# Adafruit_VS1053_Breakout.net
KiCad netlist of a schematic drawn in EAGLE
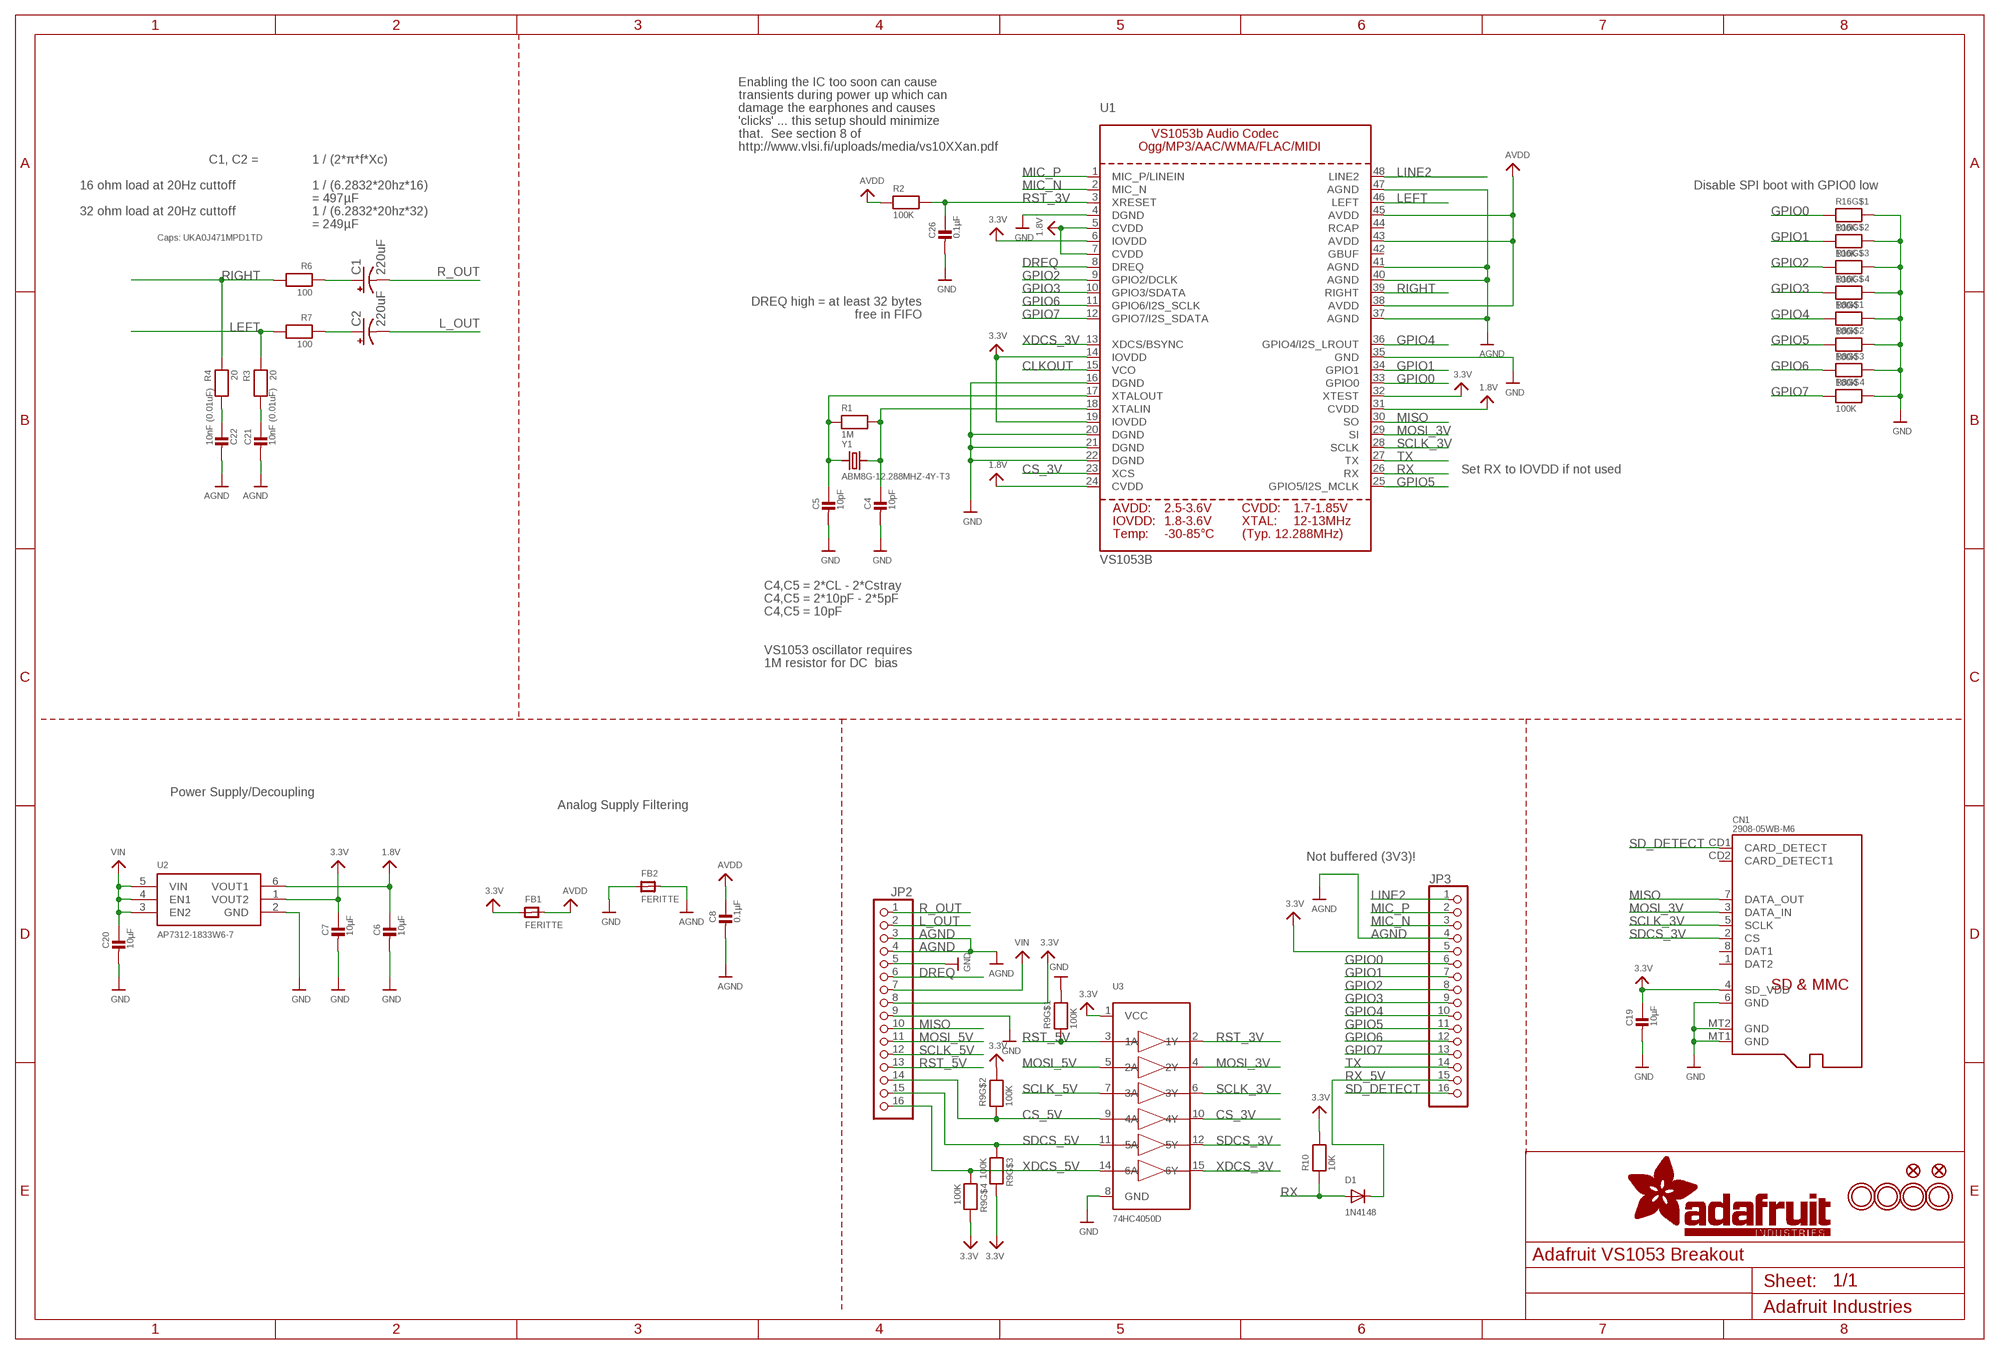
[diagram p0: schematic, sheet 1]

(export (version "E")
  (design (tool "Eeschema 10.0.6"))
  (components
    (comp (ref "C1")
      (value "220uF")
      (footprint "eagle-import:PANASONIC_C")
      (libsource (lib "eagle-import") (part "CPOL-USC"))
    )
    (comp (ref "C2")
      (value "220uF")
      (footprint "eagle-import:PANASONIC_C")
      (libsource (lib "eagle-import") (part "CPOL-USC"))
    )
    (comp (ref "C4")
      (value "10pF")
      (footprint "eagle-import:_0805MP")
      (libsource (lib "eagle-import") (part "CAP_CERAMIC_0805MP"))
    )
    (comp (ref "C5")
      (value "10pF")
      (footprint "eagle-import:_0805MP")
      (libsource (lib "eagle-import") (part "CAP_CERAMIC_0805MP"))
    )
    (comp (ref "C6")
      (value "10µF")
      (footprint "eagle-import:_0805MP")
      (libsource (lib "eagle-import") (part "CAP_CERAMIC_0805MP"))
    )
    (comp (ref "C7")
      (value "10µF")
      (footprint "eagle-import:_0805MP")
      (libsource (lib "eagle-import") (part "CAP_CERAMIC_0805MP"))
    )
    (comp (ref "C8")
      (value "0.1µF")
      (footprint "eagle-import:_0805MP")
      (libsource (lib "eagle-import") (part "CAP_CERAMIC_0805MP"))
    )
    (comp (ref "C19")
      (value "10µF")
      (footprint "eagle-import:_0805MP")
      (libsource (lib "eagle-import") (part "CAP_CERAMIC_0805MP"))
    )
    (comp (ref "C20")
      (value "10µF")
      (footprint "eagle-import:_0805MP")
      (libsource (lib "eagle-import") (part "CAP_CERAMIC_0805MP"))
    )
    (comp (ref "C21")
      (value "10nF (0.01uF)")
      (footprint "eagle-import:_0805MP")
      (libsource (lib "eagle-import") (part "CAP_CERAMIC_0805MP"))
    )
    (comp (ref "C22")
      (value "10nF (0.01uF)")
      (footprint "eagle-import:_0805MP")
      (libsource (lib "eagle-import") (part "CAP_CERAMIC_0805MP"))
    )
    (comp (ref "C26")
      (value "0.1µF")
      (footprint "eagle-import:_0805MP")
      (libsource (lib "eagle-import") (part "CAP_CERAMIC_0805MP"))
    )
    (comp (ref "CN1")
      (value "2908-05WB-M6")
      (footprint "eagle-import:MICROSD")
      (libsource (lib "eagle-import") (part "MICROSD"))
    )
    (comp (ref "D1")
      (value "1N4148")
      (footprint "eagle-import:SOD-323")
      (libsource (lib "eagle-import") (part "DIODESOD-323"))
    )
    (comp (ref "FB1")
      (value "FERITTE")
      (footprint "eagle-import:_0805MP")
      (libsource (lib "eagle-import") (part "FERRITE_0805MP"))
    )
    (comp (ref "FB2")
      (value "FERITTE")
      (footprint "eagle-import:_0805MP")
      (libsource (lib "eagle-import") (part "FERRITE_0805MP"))
    )
    (comp (ref "FID1")
      (value "FIDUCIAL\"\"")
      (footprint "eagle-import:FIDUCIAL_1MM")
      (libsource (lib "eagle-import") (part "FIDUCIAL{dblquote}{dblquote}"))
    )
    (comp (ref "FID2")
      (value "FIDUCIAL\"\"")
      (footprint "eagle-import:FIDUCIAL_1MM")
      (libsource (lib "eagle-import") (part "FIDUCIAL{dblquote}{dblquote}"))
    )
    (comp (ref "JP2")
      (value "HEADER-1X16ROUND")
      (footprint "eagle-import:1X16_ROUND")
      (libsource (lib "eagle-import") (part "HEADER-1X16ROUND"))
    )
    (comp (ref "JP3")
      (value "HEADER-1X16ROUND")
      (footprint "eagle-import:1X16_ROUND")
      (libsource (lib "eagle-import") (part "HEADER-1X16ROUND"))
    )
    (comp (ref "R1")
      (value "1M")
      (footprint "eagle-import:_0805MP")
      (libsource (lib "eagle-import") (part "RESISTOR_0805MP"))
    )
    (comp (ref "R2")
      (value "100K")
      (footprint "eagle-import:_0805MP")
      (libsource (lib "eagle-import") (part "RESISTOR_0805MP"))
    )
    (comp (ref "R3")
      (value "20")
      (footprint "eagle-import:_0805MP")
      (libsource (lib "eagle-import") (part "RESISTOR_0805MP"))
    )
    (comp (ref "R4")
      (value "20")
      (footprint "eagle-import:_0805MP")
      (libsource (lib "eagle-import") (part "RESISTOR_0805MP"))
    )
    (comp (ref "R6")
      (value "100")
      (footprint "eagle-import:_0805MP")
      (libsource (lib "eagle-import") (part "RESISTOR_0805MP"))
    )
    (comp (ref "R7")
      (value "100")
      (footprint "eagle-import:_0805MP")
      (libsource (lib "eagle-import") (part "RESISTOR_0805MP"))
    )
    (comp (ref "R8")
      (value "100K")
      (footprint "eagle-import:RESPACK_4X0603")
      (libsource (lib "eagle-import") (part "RESISTOR_4PACK"))
    )
    (comp (ref "R9")
      (value "100K")
      (footprint "eagle-import:RESPACK_4X0603")
      (libsource (lib "eagle-import") (part "RESISTOR_4PACK"))
    )
    (comp (ref "R10")
      (value "10K")
      (footprint "eagle-import:0805-NO")
      (libsource (lib "eagle-import") (part "RESISTOR0805_NOOUTLINE"))
    )
    (comp (ref "R16")
      (value "100K")
      (footprint "eagle-import:RESPACK_4X0603")
      (libsource (lib "eagle-import") (part "RESISTOR_4PACK"))
    )
    (comp (ref "U$50")
      (value "MOUNTINGHOLE3.0THIN")
      (footprint "eagle-import:MOUNTINGHOLE_3.0_PLATEDTHIN")
      (libsource (lib "eagle-import") (part "MOUNTINGHOLE3.0THIN"))
    )
    (comp (ref "U$51")
      (value "MOUNTINGHOLE3.0THIN")
      (footprint "eagle-import:MOUNTINGHOLE_3.0_PLATEDTHIN")
      (libsource (lib "eagle-import") (part "MOUNTINGHOLE3.0THIN"))
    )
    (comp (ref "U$52")
      (value "MOUNTINGHOLE3.0THIN")
      (footprint "eagle-import:MOUNTINGHOLE_3.0_PLATEDTHIN")
      (libsource (lib "eagle-import") (part "MOUNTINGHOLE3.0THIN"))
    )
    (comp (ref "U$53")
      (value "MOUNTINGHOLE3.0THIN")
      (footprint "eagle-import:MOUNTINGHOLE_3.0_PLATEDTHIN")
      (libsource (lib "eagle-import") (part "MOUNTINGHOLE3.0THIN"))
    )
    (comp (ref "U1")
      (value "VS1053B")
      (footprint "eagle-import:LQFP48")
      (libsource (lib "eagle-import") (part "VS1053B"))
    )
    (comp (ref "U2")
      (value "AP7312-1833W6-7")
      (footprint "eagle-import:SOT23-6")
      (libsource (lib "eagle-import") (part "VREG_SOT23-6_DUALAP7312"))
    )
    (comp (ref "U3")
      (value "74HC4050D")
      (footprint "eagle-import:SOIC16")
      (libsource (lib "eagle-import") (part "74HC4050D"))
    )
    (comp (ref "Y1")
      (value "ABM8G-12.288MHZ-4Y-T3")
      (footprint "eagle-import:CRYSTAL_3.2X2.5")
      (libsource (lib "eagle-import") (part "CRYSTAL3.2X2.5"))
    )
  )
  (nets
    (net (code "1") (name "/CLKOUT") (class "Default")
      (node (ref "U1") (pin "15") (pinfunction "VCO_15") (pintype "bidirectional"))
    )
    (net (code "2") (name "/CS_3V") (class "Default")
      (node (ref "U1") (pin "23") (pinfunction "XCS_23") (pintype "bidirectional"))
      (node (ref "U3") (pin "10") (pinfunction "4Y_10") (pintype "bidirectional"))
    )
    (net (code "3") (name "/CS_5V") (class "Default")
      (node (ref "JP2") (pin "14") (pinfunction "14_14") (pintype "passive"))
      (node (ref "R9") (pin "2") (pinfunction "1_2") (pintype "passive"))
      (node (ref "U3") (pin "9") (pinfunction "4A_9") (pintype "bidirectional"))
    )
    (net (code "4") (name "/DREQ") (class "Default")
      (node (ref "JP2") (pin "6") (pinfunction "6_6") (pintype "passive"))
      (node (ref "U1") (pin "8") (pinfunction "DREQ_8") (pintype "bidirectional"))
    )
    (net (code "5") (name "/GPIO0") (class "Default")
      (node (ref "JP3") (pin "6") (pinfunction "6_6") (pintype "passive"))
      (node (ref "R16") (pin "1") (pinfunction "1_1") (pintype "passive"))
      (node (ref "U1") (pin "33") (pinfunction "GPIO0_33") (pintype "bidirectional"))
    )
    (net (code "6") (name "/GPIO1") (class "Default")
      (node (ref "JP3") (pin "7") (pinfunction "7_7") (pintype "passive"))
      (node (ref "R16") (pin "2") (pinfunction "1_2") (pintype "passive"))
      (node (ref "U1") (pin "34") (pinfunction "GPIO1_34") (pintype "bidirectional"))
    )
    (net (code "7") (name "/GPIO2") (class "Default")
      (node (ref "JP3") (pin "8") (pinfunction "8_8") (pintype "passive"))
      (node (ref "R16") (pin "3") (pinfunction "1_3") (pintype "passive"))
      (node (ref "U1") (pin "9") (pinfunction "GPIO2/DCLK_9") (pintype "bidirectional"))
    )
    (net (code "8") (name "/GPIO3") (class "Default")
      (node (ref "JP3") (pin "9") (pinfunction "9_9") (pintype "passive"))
      (node (ref "R16") (pin "4") (pinfunction "1_4") (pintype "passive"))
      (node (ref "U1") (pin "10") (pinfunction "GPIO3/SDATA_10") (pintype "bidirectional"))
    )
    (net (code "9") (name "/GPIO4") (class "Default")
      (node (ref "JP3") (pin "10") (pinfunction "10_10") (pintype "passive"))
      (node (ref "R8") (pin "1") (pinfunction "1_1") (pintype "passive"))
      (node (ref "U1") (pin "36") (pinfunction "GPIO4/I2S_LROUT_36") (pintype "bidirectional"))
    )
    (net (code "10") (name "/GPIO5") (class "Default")
      (node (ref "JP3") (pin "11") (pinfunction "11_11") (pintype "passive"))
      (node (ref "R8") (pin "2") (pinfunction "1_2") (pintype "passive"))
      (node (ref "U1") (pin "25") (pinfunction "GPIO5/I2S_MCLK_25") (pintype "bidirectional"))
    )
    (net (code "11") (name "/GPIO6") (class "Default")
      (node (ref "JP3") (pin "12") (pinfunction "12_12") (pintype "passive"))
      (node (ref "R8") (pin "3") (pinfunction "1_3") (pintype "passive"))
      (node (ref "U1") (pin "11") (pinfunction "GPIO6/I2S_SCLK_11") (pintype "bidirectional"))
    )
    (net (code "12") (name "/GPIO7") (class "Default")
      (node (ref "JP3") (pin "13") (pinfunction "13_13") (pintype "passive"))
      (node (ref "R8") (pin "4") (pinfunction "1_4") (pintype "passive"))
      (node (ref "U1") (pin "12") (pinfunction "GPIO7/I2S_SDATA_12") (pintype "bidirectional"))
    )
    (net (code "13") (name "/LEFT") (class "Default")
      (node (ref "R3") (pin "1") (pinfunction "1_1") (pintype "passive"))
      (node (ref "R7") (pin "2") (pinfunction "2_2") (pintype "passive"))
      (node (ref "U1") (pin "46") (pinfunction "LEFT_46") (pintype "bidirectional"))
    )
    (net (code "14") (name "/LINE2") (class "Default")
      (node (ref "JP3") (pin "1") (pinfunction "1_1") (pintype "passive"))
      (node (ref "U1") (pin "48") (pinfunction "LINE2_48") (pintype "bidirectional"))
    )
    (net (code "15") (name "/L_OUT") (class "Default")
      (node (ref "C2") (pin "-") (pinfunction "-_-") (pintype "passive"))
      (node (ref "JP2") (pin "2") (pinfunction "2_2") (pintype "passive"))
    )
    (net (code "16") (name "/MIC_N") (class "Default")
      (node (ref "JP3") (pin "3") (pinfunction "3_3") (pintype "passive"))
      (node (ref "U1") (pin "2") (pinfunction "MIC_N_2") (pintype "bidirectional"))
    )
    (net (code "17") (name "/MIC_P") (class "Default")
      (node (ref "JP3") (pin "2") (pinfunction "2_2") (pintype "passive"))
      (node (ref "U1") (pin "1") (pinfunction "MIC_P/LINEIN_1") (pintype "bidirectional"))
    )
    (net (code "18") (name "/MISO") (class "Default")
      (node (ref "CN1") (pin "7") (pinfunction "DATA_OUT_7") (pintype "output"))
      (node (ref "JP2") (pin "10") (pinfunction "10_10") (pintype "passive"))
      (node (ref "U1") (pin "30") (pinfunction "SO_30") (pintype "bidirectional"))
    )
    (net (code "19") (name "/MOSI_3V") (class "Default")
      (node (ref "CN1") (pin "3") (pinfunction "DATA_IN_3") (pintype "input"))
      (node (ref "U1") (pin "29") (pinfunction "SI_29") (pintype "bidirectional"))
      (node (ref "U3") (pin "4") (pinfunction "2Y_4") (pintype "bidirectional"))
    )
    (net (code "20") (name "/MOSI_5V") (class "Default")
      (node (ref "JP2") (pin "11") (pinfunction "11_11") (pintype "passive"))
      (node (ref "U3") (pin "5") (pinfunction "2A_5") (pintype "bidirectional"))
    )
    (net (code "21") (name "/RIGHT") (class "Default")
      (node (ref "R4") (pin "1") (pinfunction "1_1") (pintype "passive"))
      (node (ref "R6") (pin "2") (pinfunction "2_2") (pintype "passive"))
      (node (ref "U1") (pin "39") (pinfunction "RIGHT_39") (pintype "bidirectional"))
    )
    (net (code "22") (name "/RST_3V") (class "Default")
      (node (ref "C26") (pin "1") (pinfunction "1_1") (pintype "passive"))
      (node (ref "R2") (pin "2") (pinfunction "2_2") (pintype "passive"))
      (node (ref "U1") (pin "3") (pinfunction "XRESET_3") (pintype "bidirectional"))
      (node (ref "U3") (pin "2") (pinfunction "1Y_2") (pintype "bidirectional"))
    )
    (net (code "23") (name "/RST_5V") (class "Default")
      (node (ref "JP2") (pin "13") (pinfunction "13_13") (pintype "passive"))
      (node (ref "R9") (pin "1") (pinfunction "1_1") (pintype "passive"))
      (node (ref "U3") (pin "3") (pinfunction "1A_3") (pintype "bidirectional"))
    )
    (net (code "24") (name "/RX") (class "Default")
      (node (ref "D1") (pin "A") (pinfunction "A_A") (pintype "passive"))
      (node (ref "R10") (pin "1") (pinfunction "1_1") (pintype "passive"))
      (node (ref "U1") (pin "26") (pinfunction "RX_26") (pintype "bidirectional"))
    )
    (net (code "25") (name "/RX_5V") (class "Default")
      (node (ref "D1") (pin "C") (pinfunction "C_C") (pintype "passive"))
      (node (ref "JP3") (pin "15") (pinfunction "15_15") (pintype "passive"))
    )
    (net (code "26") (name "/R_OUT") (class "Default")
      (node (ref "C1") (pin "-") (pinfunction "-_-") (pintype "passive"))
      (node (ref "JP2") (pin "1") (pinfunction "1_1") (pintype "passive"))
    )
    (net (code "27") (name "/SCLK_3V") (class "Default")
      (node (ref "CN1") (pin "5") (pinfunction "SCLK_5") (pintype "input"))
      (node (ref "U1") (pin "28") (pinfunction "SCLK_28") (pintype "bidirectional"))
      (node (ref "U3") (pin "6") (pinfunction "3Y_6") (pintype "bidirectional"))
    )
    (net (code "28") (name "/SCLK_5V") (class "Default")
      (node (ref "JP2") (pin "12") (pinfunction "12_12") (pintype "passive"))
      (node (ref "U3") (pin "7") (pinfunction "3A_7") (pintype "bidirectional"))
    )
    (net (code "29") (name "/SDCS_3V") (class "Default")
      (node (ref "CN1") (pin "2") (pinfunction "CS_2") (pintype "input"))
      (node (ref "U3") (pin "12") (pinfunction "5Y_12") (pintype "bidirectional"))
    )
    (net (code "30") (name "/SDCS_5V") (class "Default")
      (node (ref "JP2") (pin "15") (pinfunction "15_15") (pintype "passive"))
      (node (ref "R9") (pin "3") (pinfunction "1_3") (pintype "passive"))
      (node (ref "U3") (pin "11") (pinfunction "5A_11") (pintype "bidirectional"))
    )
    (net (code "31") (name "/SD_DETECT") (class "Default")
      (node (ref "CN1") (pin "CD1") (pinfunction "CARD_DETECT_CD1") (pintype "passive"))
      (node (ref "JP3") (pin "16") (pinfunction "16_16") (pintype "passive"))
    )
    (net (code "32") (name "/TX") (class "Default")
      (node (ref "JP3") (pin "14") (pinfunction "14_14") (pintype "passive"))
      (node (ref "U1") (pin "27") (pinfunction "TX_27") (pintype "bidirectional"))
    )
    (net (code "33") (name "/XDCS_3V") (class "Default")
      (node (ref "U1") (pin "13") (pinfunction "XDCS/BSYNC_13") (pintype "bidirectional"))
      (node (ref "U3") (pin "15") (pinfunction "6Y_15") (pintype "bidirectional"))
    )
    (net (code "34") (name "/XDCS_5V") (class "Default")
      (node (ref "JP2") (pin "16") (pinfunction "16_16") (pintype "passive"))
      (node (ref "R9") (pin "4") (pinfunction "1_4") (pintype "passive"))
      (node (ref "U3") (pin "14") (pinfunction "6A_14") (pintype "bidirectional"))
    )
    (net (code "35") (name "1.8V") (class "Default")
      (node (ref "C6") (pin "1") (pinfunction "1_1") (pintype "passive"))
      (node (ref "U1") (pin "24") (pinfunction "CVDD_24") (pintype "power_in"))
      (node (ref "U1") (pin "31") (pinfunction "CVDD_31") (pintype "power_in"))
      (node (ref "U1") (pin "5") (pinfunction "CVDD_5") (pintype "power_in"))
      (node (ref "U1") (pin "7") (pinfunction "CVDD_7") (pintype "power_in"))
      (node (ref "U2") (pin "6") (pinfunction "VOUT1_6") (pintype "bidirectional"))
    )
    (net (code "36") (name "3.3V") (class "Default")
      (node (ref "C19") (pin "1") (pinfunction "1_1") (pintype "passive"))
      (node (ref "C7") (pin "1") (pinfunction "1_1") (pintype "passive"))
      (node (ref "CN1") (pin "4") (pinfunction "SD_VDD_4") (pintype "power_in"))
      (node (ref "FB1") (pin "1") (pinfunction "P$1_1") (pintype "passive"))
      (node (ref "JP2") (pin "8") (pinfunction "8_8") (pintype "passive"))
      (node (ref "JP3") (pin "5") (pinfunction "5_5") (pintype "passive"))
      (node (ref "R10") (pin "2") (pinfunction "2_2") (pintype "passive"))
      (node (ref "R9") (pin "5") (pinfunction "2_5") (pintype "passive"))
      (node (ref "R9") (pin "6") (pinfunction "2_6") (pintype "passive"))
      (node (ref "R9") (pin "7") (pinfunction "2_7") (pintype "passive"))
      (node (ref "U1") (pin "14") (pinfunction "IOVDD_14") (pintype "power_in"))
      (node (ref "U1") (pin "19") (pinfunction "IOVDD_19") (pintype "power_in"))
      (node (ref "U1") (pin "32") (pinfunction "XTEST_32") (pintype "bidirectional"))
      (node (ref "U1") (pin "6") (pinfunction "IOVDD_6") (pintype "power_in"))
      (node (ref "U2") (pin "1") (pinfunction "VOUT2_1") (pintype "bidirectional"))
      (node (ref "U3") (pin "1") (pinfunction "VCC_1") (pintype "bidirectional"))
    )
    (net (code "37") (name "AGND") (class "Default")
      (node (ref "C21") (pin "2") (pinfunction "2_2") (pintype "passive"))
      (node (ref "C22") (pin "2") (pinfunction "2_2") (pintype "passive"))
      (node (ref "C8") (pin "2") (pinfunction "2_2") (pintype "passive"))
      (node (ref "FB2") (pin "2") (pinfunction "P$2_2") (pintype "passive"))
      (node (ref "JP2") (pin "3") (pinfunction "3_3") (pintype "passive"))
      (node (ref "JP2") (pin "4") (pinfunction "4_4") (pintype "passive"))
      (node (ref "JP3") (pin "4") (pinfunction "4_4") (pintype "passive"))
      (node (ref "U1") (pin "37") (pinfunction "AGND_37") (pintype "power_in"))
      (node (ref "U1") (pin "40") (pinfunction "AGND_40") (pintype "power_in"))
      (node (ref "U1") (pin "41") (pinfunction "AGND_41") (pintype "power_in"))
      (node (ref "U1") (pin "47") (pinfunction "AGND_47") (pintype "power_in"))
    )
    (net (code "38") (name "AVDD") (class "Default")
      (node (ref "C8") (pin "1") (pinfunction "1_1") (pintype "passive"))
      (node (ref "FB1") (pin "2") (pinfunction "P$2_2") (pintype "passive"))
      (node (ref "R2") (pin "1") (pinfunction "1_1") (pintype "passive"))
      (node (ref "U1") (pin "38") (pinfunction "AVDD_38") (pintype "power_in"))
      (node (ref "U1") (pin "43") (pinfunction "AVDD_43") (pintype "power_in"))
      (node (ref "U1") (pin "45") (pinfunction "AVDD_45") (pintype "power_in"))
    )
    (net (code "39") (name "GND") (class "Default")
      (node (ref "C19") (pin "2") (pinfunction "2_2") (pintype "passive"))
      (node (ref "C20") (pin "2") (pinfunction "2_2") (pintype "passive"))
      (node (ref "C26") (pin "2") (pinfunction "2_2") (pintype "passive"))
      (node (ref "C4") (pin "2") (pinfunction "2_2") (pintype "passive"))
      (node (ref "C5") (pin "2") (pinfunction "2_2") (pintype "passive"))
      (node (ref "C6") (pin "2") (pinfunction "2_2") (pintype "passive"))
      (node (ref "C7") (pin "2") (pinfunction "2_2") (pintype "passive"))
      (node (ref "CN1") (pin "6") (pinfunction "GND_6") (pintype "power_in"))
      (node (ref "CN1") (pin "MT1") (pinfunction "GND_MT1") (pintype "power_in"))
      (node (ref "CN1") (pin "MT2") (pinfunction "GND_MT2") (pintype "power_in"))
      (node (ref "FB2") (pin "1") (pinfunction "P$1_1") (pintype "passive"))
      (node (ref "JP2") (pin "5") (pinfunction "5_5") (pintype "passive"))
      (node (ref "JP2") (pin "9") (pinfunction "9_9") (pintype "passive"))
      (node (ref "R16") (pin "5") (pinfunction "2_5") (pintype "passive"))
      (node (ref "R16") (pin "6") (pinfunction "2_6") (pintype "passive"))
      (node (ref "R16") (pin "7") (pinfunction "2_7") (pintype "passive"))
      (node (ref "R16") (pin "8") (pinfunction "2_8") (pintype "passive"))
      (node (ref "R8") (pin "5") (pinfunction "2_5") (pintype "passive"))
      (node (ref "R8") (pin "6") (pinfunction "2_6") (pintype "passive"))
      (node (ref "R8") (pin "7") (pinfunction "2_7") (pintype "passive"))
      (node (ref "R8") (pin "8") (pinfunction "2_8") (pintype "passive"))
      (node (ref "R9") (pin "8") (pinfunction "2_8") (pintype "passive"))
      (node (ref "U1") (pin "16") (pinfunction "DGND_16") (pintype "power_in"))
      (node (ref "U1") (pin "20") (pinfunction "DGND_20") (pintype "power_in"))
      (node (ref "U1") (pin "21") (pinfunction "DGND_21") (pintype "power_in"))
      (node (ref "U1") (pin "22") (pinfunction "DGND_22") (pintype "power_in"))
      (node (ref "U1") (pin "35") (pinfunction "GND_35") (pintype "power_in"))
      (node (ref "U1") (pin "4") (pinfunction "DGND_4") (pintype "power_in"))
      (node (ref "U2") (pin "2") (pinfunction "GND_2") (pintype "bidirectional"))
      (node (ref "U3") (pin "8") (pinfunction "GND_8") (pintype "bidirectional"))
    )
    (net (code "40") (name "Net-(C1-Pad+)") (class "Default")
      (node (ref "C1") (pin "+") (pinfunction "+_+") (pintype "passive"))
      (node (ref "R6") (pin "1") (pinfunction "1_1") (pintype "passive"))
    )
    (net (code "41") (name "Net-(C2-Pad+)") (class "Default")
      (node (ref "C2") (pin "+") (pinfunction "+_+") (pintype "passive"))
      (node (ref "R7") (pin "1") (pinfunction "1_1") (pintype "passive"))
    )
    (net (code "42") (name "Net-(C21-Pad1)") (class "Default")
      (node (ref "C21") (pin "1") (pinfunction "1_1") (pintype "passive"))
      (node (ref "R3") (pin "2") (pinfunction "2_2") (pintype "passive"))
    )
    (net (code "43") (name "Net-(C22-Pad1)") (class "Default")
      (node (ref "C22") (pin "1") (pinfunction "1_1") (pintype "passive"))
      (node (ref "R4") (pin "2") (pinfunction "2_2") (pintype "passive"))
    )
    (net (code "44") (name "Net-(U1-XTALIN)") (class "Default")
      (node (ref "C4") (pin "1") (pinfunction "1_1") (pintype "passive"))
      (node (ref "R1") (pin "2") (pinfunction "2_2") (pintype "passive"))
      (node (ref "U1") (pin "18") (pinfunction "XTALIN_18") (pintype "input"))
      (node (ref "Y1") (pin "2") (pinfunction "2_2") (pintype "passive"))
    )
    (net (code "45") (name "Net-(U1-XTALOUT)") (class "Default")
      (node (ref "C5") (pin "1") (pinfunction "1_1") (pintype "passive"))
      (node (ref "R1") (pin "1") (pinfunction "1_1") (pintype "passive"))
      (node (ref "U1") (pin "17") (pinfunction "XTALOUT_17") (pintype "output"))
      (node (ref "Y1") (pin "1") (pinfunction "1_1") (pintype "passive"))
    )
    (net (code "46") (name "VIN") (class "Default")
      (node (ref "C20") (pin "1") (pinfunction "1_1") (pintype "passive"))
      (node (ref "JP2") (pin "7") (pinfunction "7_7") (pintype "passive"))
      (node (ref "U2") (pin "3") (pinfunction "EN2_3") (pintype "bidirectional"))
      (node (ref "U2") (pin "4") (pinfunction "EN1_4") (pintype "bidirectional"))
      (node (ref "U2") (pin "5") (pinfunction "VIN_5") (pintype "bidirectional"))
    )
    (net (code "47") (name "unconnected-(CN1-CARD_DETECT1-PadCD2)") (class "Default")
      (node (ref "CN1") (pin "CD2") (pinfunction "CARD_DETECT1_CD2") (pintype "passive"))
    )
    (net (code "48") (name "unconnected-(CN1-DAT1-Pad8)") (class "Default")
      (node (ref "CN1") (pin "8") (pinfunction "DAT1_8") (pintype "bidirectional"))
    )
    (net (code "49") (name "unconnected-(CN1-DAT2-Pad1)") (class "Default")
      (node (ref "CN1") (pin "1") (pinfunction "DAT2_1") (pintype "bidirectional"))
    )
    (net (code "50") (name "unconnected-(U1-GBUF-Pad42)") (class "Default")
      (node (ref "U1") (pin "42") (pinfunction "GBUF_42") (pintype "bidirectional"))
    )
    (net (code "51") (name "unconnected-(U1-RCAP-Pad44)") (class "Default")
      (node (ref "U1") (pin "44") (pinfunction "RCAP_44") (pintype "bidirectional"))
    )
  )
)
